# schematic.net
KiCad netlist of a schematic drawn in EasyEDA
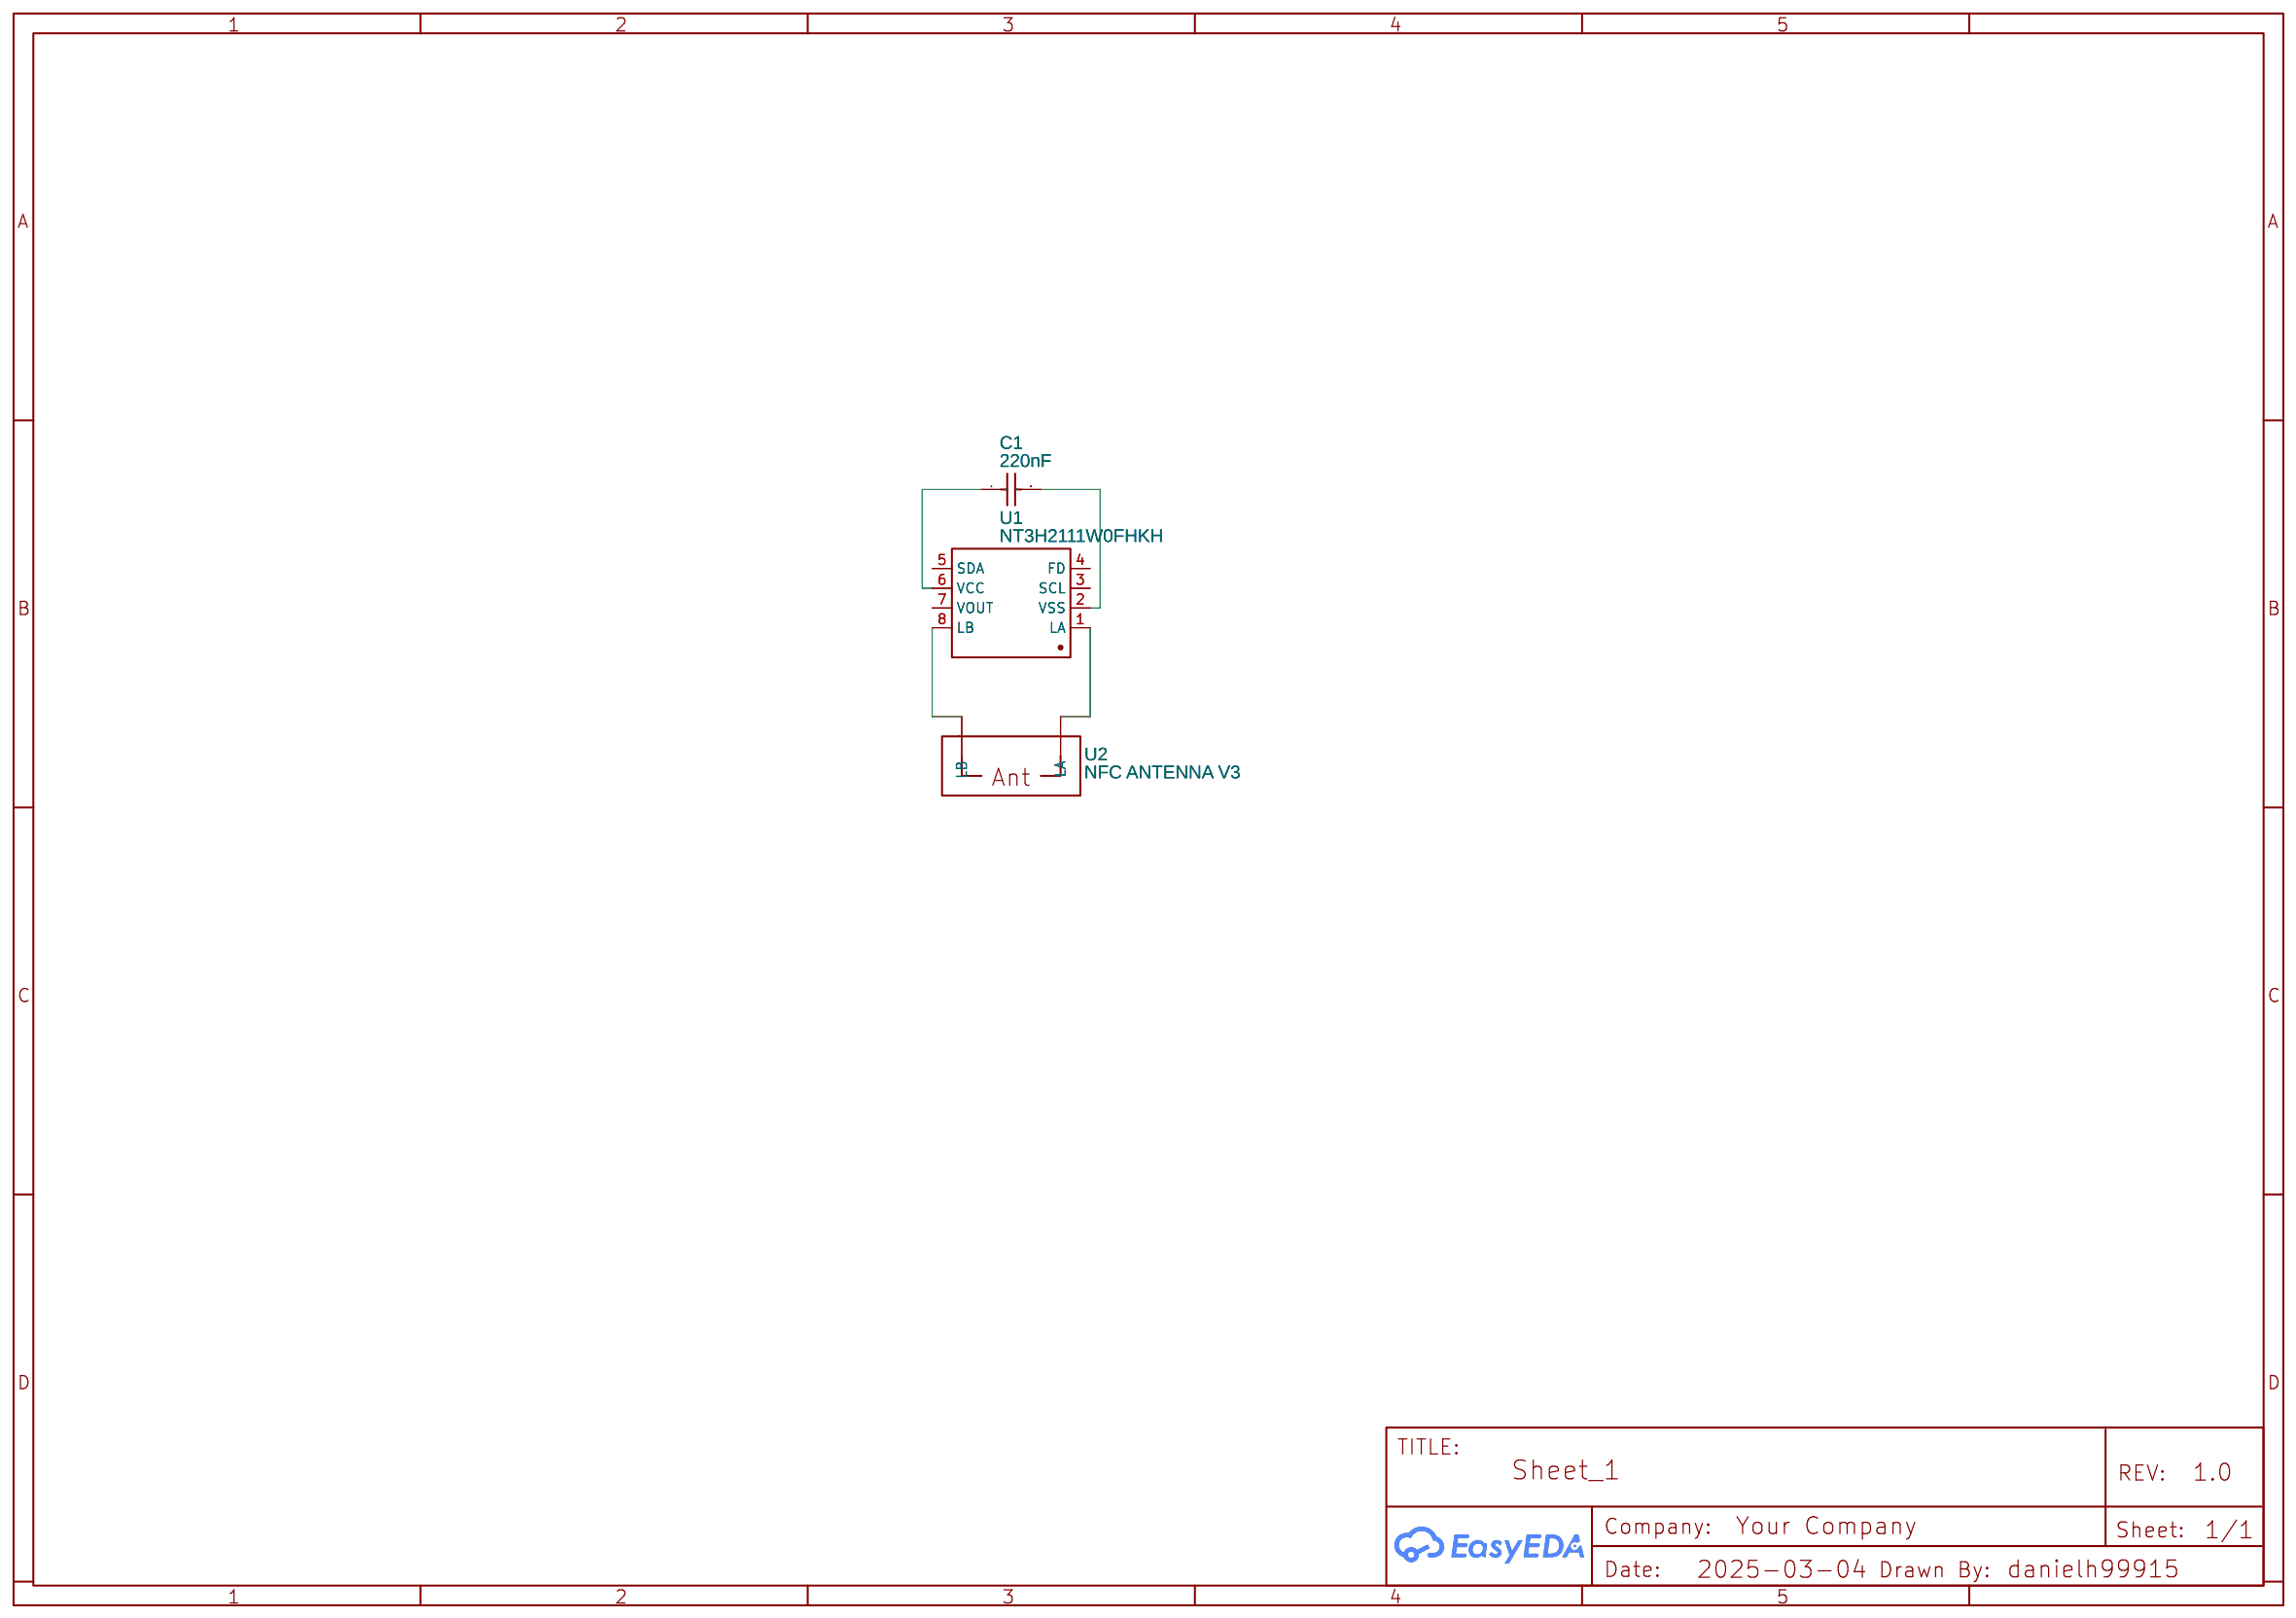
[diagram p0: schematic sheet]

(export (version "E")
  (design (tool "Eeschema 10.0.6"))
  (components
    (comp (ref "C1")
      (value "220nF")
      (fields (field (name "Manufacturer Part") "C1005X5R0J224KT000F") (field (name "Manufacturer") "TDK"))
      (libsource (lib "") (part "C1005X5R0J224KT000F"))
    )
    (comp (ref "U1")
      (value "NT3H2111W0FHKH")
      (fields (field (name "Manufacturer") "NXP(恩智浦)"))
      (libsource (lib "") (part "NT3H2111W0FHKH"))
    )
    (comp (ref "U2") (value "NFC ANTENNA V3") (libsource (lib "") (part "NFC ANTENNA V3")))
  )
  (nets
    (net (code "1") (name "Net-(U1-LA)") (class "Default")
      (node (ref "U1") (pin "1") (pinfunction "LA_1") (pintype "unspecified"))
      (node (ref "U2") (pin "LA") (pinfunction "LA_LA") (pintype "unspecified"))
    )
    (net (code "2") (name "Net-(U1-LB)") (class "Default")
      (node (ref "U1") (pin "8") (pinfunction "LB_8") (pintype "unspecified"))
      (node (ref "U2") (pin "LB") (pinfunction "LB_LB") (pintype "unspecified"))
    )
    (net (code "3") (name "Net-(U1-VCC)") (class "Default")
      (node (ref "C1") (pin "1") (pinfunction "1_1") (pintype "input"))
      (node (ref "U1") (pin "6") (pinfunction "VCC_6") (pintype "unspecified"))
    )
    (net (code "4") (name "Net-(U1-VSS)") (class "Default")
      (node (ref "C1") (pin "2") (pinfunction "2_2") (pintype "input"))
      (node (ref "U1") (pin "2") (pinfunction "VSS_2") (pintype "unspecified"))
    )
    (net (code "5") (name "unconnected-(U1-FD-Pad4)") (class "Default")
      (node (ref "U1") (pin "4") (pinfunction "FD_4") (pintype "unspecified"))
    )
    (net (code "6") (name "unconnected-(U1-SCL-Pad3)") (class "Default")
      (node (ref "U1") (pin "3") (pinfunction "SCL_3") (pintype "unspecified"))
    )
    (net (code "7") (name "unconnected-(U1-SDA-Pad5)") (class "Default")
      (node (ref "U1") (pin "5") (pinfunction "SDA_5") (pintype "unspecified"))
    )
    (net (code "8") (name "unconnected-(U1-VOUT-Pad7)") (class "Default")
      (node (ref "U1") (pin "7") (pinfunction "VOUT_7") (pintype "unspecified"))
    )
  )
)
